# Jetson_Breakout.net
KiCad netlist of a schematic drawn in EAGLE
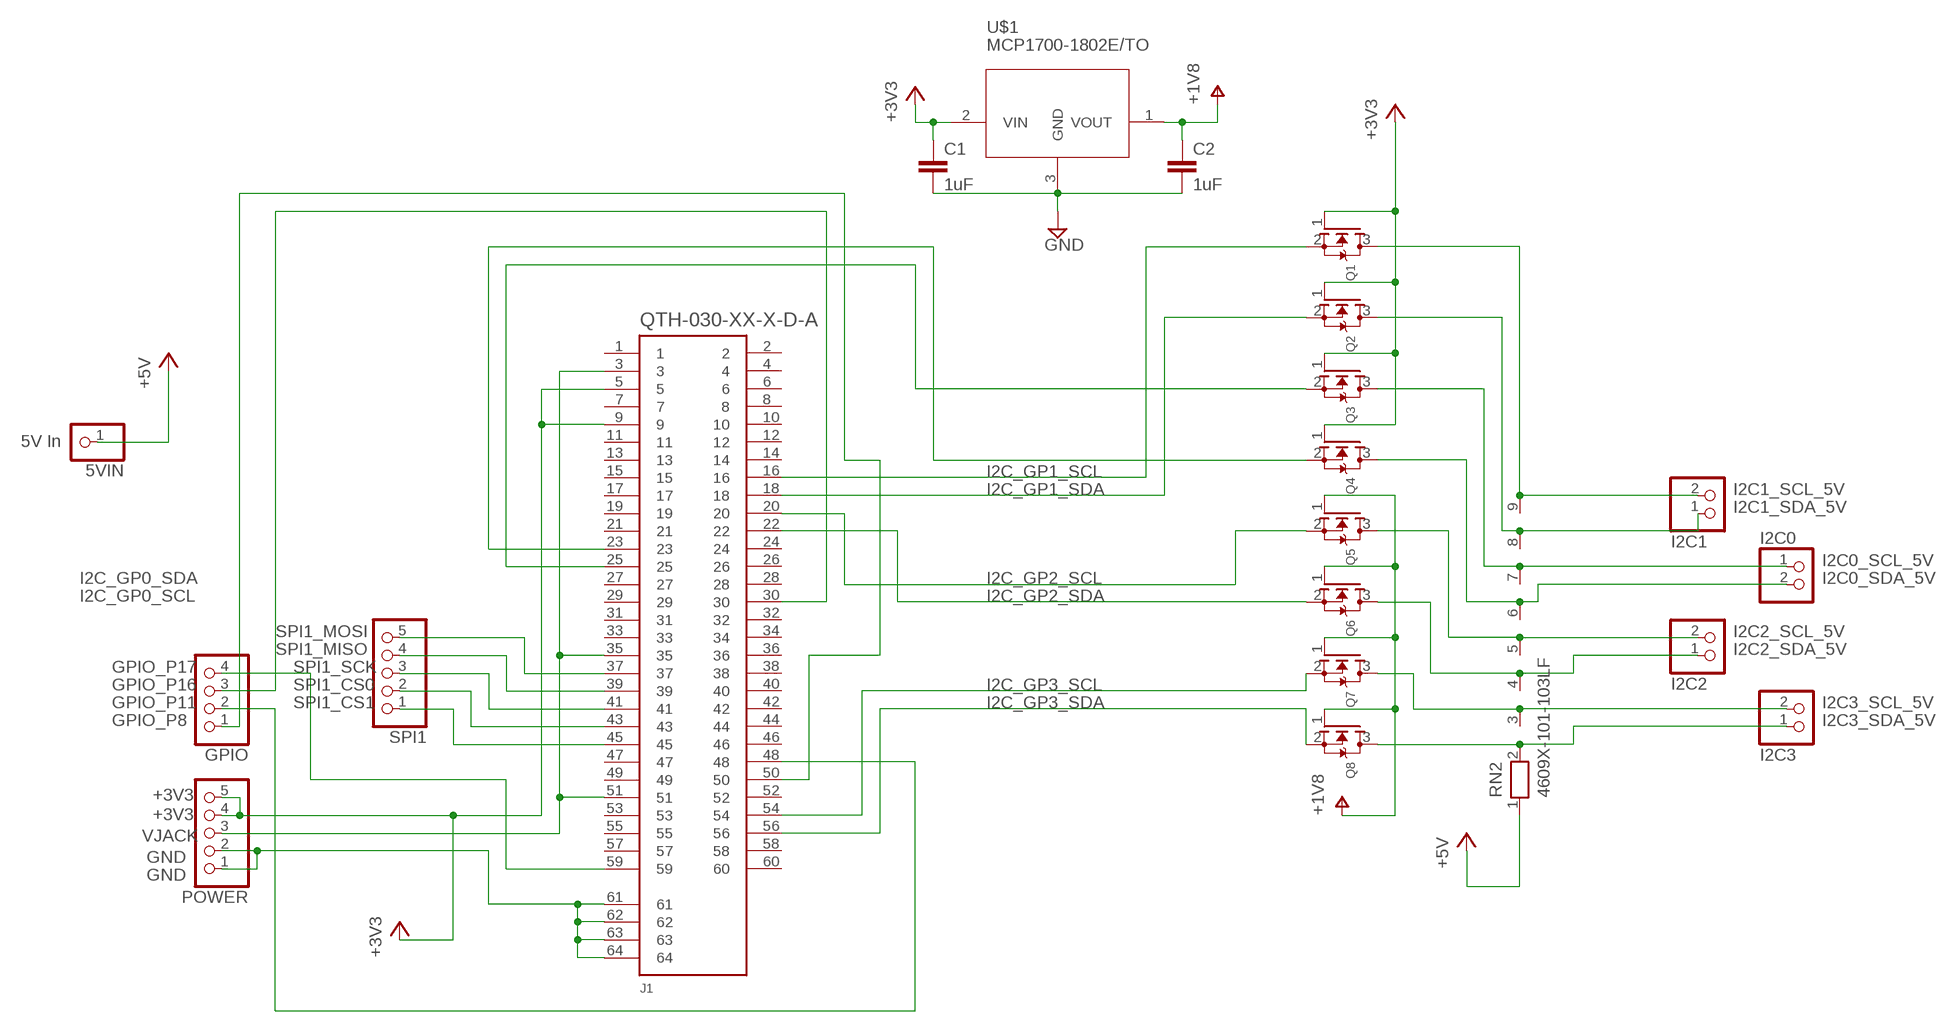
[diagram p0: schematic, sheet 1]

(export (version "E")
  (design (tool "Eeschema 10.0.6"))
  (components
    (comp (ref "5VIN")
      (value "PINHD-1X1")
      (footprint "eagle-import:1X01")
      (libsource (lib "eagle-import") (part "PINHD-1X1"))
    )
    (comp (ref "C1")
      (value "1uF")
      (footprint "eagle-import:C050-025X075")
      (libsource (lib "eagle-import") (part "C-EU050-025X075"))
    )
    (comp (ref "C2")
      (value "1uF")
      (footprint "eagle-import:C050-025X075")
      (libsource (lib "eagle-import") (part "C-EU050-025X075"))
    )
    (comp (ref "GPIO")
      (value "PINHD-1X4")
      (footprint "eagle-import:1X04")
      (libsource (lib "eagle-import") (part "PINHD-1X4"))
    )
    (comp (ref "I2C0")
      (value "PINHD-1X2")
      (footprint "eagle-import:1X02")
      (libsource (lib "eagle-import") (part "PINHD-1X2"))
    )
    (comp (ref "I2C1")
      (value "PINHD-1X2")
      (footprint "eagle-import:1X02")
      (libsource (lib "eagle-import") (part "PINHD-1X2"))
    )
    (comp (ref "I2C2")
      (value "PINHD-1X2")
      (footprint "eagle-import:1X02")
      (libsource (lib "eagle-import") (part "PINHD-1X2"))
    )
    (comp (ref "I2C3")
      (value "PINHD-1X2")
      (footprint "eagle-import:1X02")
      (libsource (lib "eagle-import") (part "PINHD-1X2"))
    )
    (comp (ref "J1")
      (value "QTH-030-XX-X-D-A")
      (footprint "eagle-import:QTH-030-XX-X-D-A")
      (libsource (lib "eagle-import") (part "QTH-030-XX-X-D-A"))
    )
    (comp (ref "POWER")
      (value "PINHD-1X5")
      (footprint "eagle-import:1X05")
      (libsource (lib "eagle-import") (part "PINHD-1X5"))
    )
    (comp (ref "Q1")
      (value "MOSFET-NREFLOW")
      (footprint "eagle-import:SOT23")
      (libsource (lib "eagle-import") (part "MOSFET-NREFLOW"))
    )
    (comp (ref "Q2")
      (value "MOSFET-NREFLOW")
      (footprint "eagle-import:SOT23")
      (libsource (lib "eagle-import") (part "MOSFET-NREFLOW"))
    )
    (comp (ref "Q3")
      (value "MOSFET-NREFLOW")
      (footprint "eagle-import:SOT23")
      (libsource (lib "eagle-import") (part "MOSFET-NREFLOW"))
    )
    (comp (ref "Q4")
      (value "MOSFET-NREFLOW")
      (footprint "eagle-import:SOT23")
      (libsource (lib "eagle-import") (part "MOSFET-NREFLOW"))
    )
    (comp (ref "Q5")
      (value "MOSFET-NREFLOW")
      (footprint "eagle-import:SOT23")
      (libsource (lib "eagle-import") (part "MOSFET-NREFLOW"))
    )
    (comp (ref "Q6")
      (value "MOSFET-NREFLOW")
      (footprint "eagle-import:SOT23")
      (libsource (lib "eagle-import") (part "MOSFET-NREFLOW"))
    )
    (comp (ref "Q7")
      (value "MOSFET-NREFLOW")
      (footprint "eagle-import:SOT23")
      (libsource (lib "eagle-import") (part "MOSFET-NREFLOW"))
    )
    (comp (ref "Q8")
      (value "MOSFET-NREFLOW")
      (footprint "eagle-import:SOT23")
      (libsource (lib "eagle-import") (part "MOSFET-NREFLOW"))
    )
    (comp (ref "RN2")
      (value "4609X-101-103LF")
      (footprint "eagle-import:RN-9")
      (libsource (lib "eagle-import") (part "RN08"))
    )
    (comp (ref "SPI1")
      (value "PINHD-1X5")
      (footprint "eagle-import:1X05")
      (libsource (lib "eagle-import") (part "PINHD-1X5"))
    )
    (comp (ref "U$1")
      (value "MCP1700-1802E/TO")
      (footprint "eagle-import:TO92")
      (libsource (lib "eagle-import") (part "MCP1700-1802E/TO"))
    )
  )
  (nets
    (net (code "1") (name "+1V8") (class "Default")
      (node (ref "C2") (pin "1") (pinfunction "1_1") (pintype "passive"))
      (node (ref "Q5") (pin "1") (pinfunction "G_1") (pintype "bidirectional"))
      (node (ref "Q6") (pin "1") (pinfunction "G_1") (pintype "bidirectional"))
      (node (ref "Q7") (pin "1") (pinfunction "G_1") (pintype "bidirectional"))
      (node (ref "Q8") (pin "1") (pinfunction "G_1") (pintype "bidirectional"))
      (node (ref "U$1") (pin "1") (pinfunction "VOUT_1") (pintype "power_in"))
    )
    (net (code "2") (name "+3V3") (class "Default")
      (node (ref "C1") (pin "1") (pinfunction "1_1") (pintype "passive"))
      (node (ref "J1") (pin "5") (pinfunction "5_5") (pintype "bidirectional"))
      (node (ref "J1") (pin "9") (pinfunction "9_9") (pintype "bidirectional"))
      (node (ref "POWER") (pin "4") (pinfunction "4_4") (pintype "passive"))
      (node (ref "POWER") (pin "5") (pinfunction "5_5") (pintype "passive"))
      (node (ref "Q1") (pin "1") (pinfunction "G_1") (pintype "bidirectional"))
      (node (ref "Q2") (pin "1") (pinfunction "G_1") (pintype "bidirectional"))
      (node (ref "Q3") (pin "1") (pinfunction "G_1") (pintype "bidirectional"))
      (node (ref "Q4") (pin "1") (pinfunction "G_1") (pintype "bidirectional"))
      (node (ref "U$1") (pin "2") (pinfunction "VIN_2") (pintype "power_in"))
    )
    (net (code "3") (name "+5V") (class "Default")
      (node (ref "5VIN") (pin "1") (pinfunction "1_1") (pintype "passive"))
      (node (ref "RN2") (pin "1") (pinfunction "1_1") (pintype "passive"))
    )
    (net (code "4") (name "/GPIO_P8") (class "Default")
      (node (ref "GPIO") (pin "1") (pinfunction "1_1") (pintype "passive"))
      (node (ref "J1") (pin "50") (pinfunction "50_50") (pintype "bidirectional"))
    )
    (net (code "5") (name "/GPIO_P11") (class "Default")
      (node (ref "GPIO") (pin "2") (pinfunction "2_2") (pintype "passive"))
      (node (ref "J1") (pin "48") (pinfunction "48_48") (pintype "bidirectional"))
    )
    (net (code "6") (name "/GPIO_P16") (class "Default")
      (node (ref "GPIO") (pin "3") (pinfunction "3_3") (pintype "passive"))
      (node (ref "J1") (pin "30") (pinfunction "30_30") (pintype "bidirectional"))
    )
    (net (code "7") (name "/GPIO_P17") (class "Default")
      (node (ref "GPIO") (pin "4") (pinfunction "4_4") (pintype "passive"))
      (node (ref "J1") (pin "59") (pinfunction "59_59") (pintype "bidirectional"))
    )
    (net (code "8") (name "/I2C0_SCL_5V") (class "Default")
      (node (ref "I2C0") (pin "1") (pinfunction "1_1") (pintype "passive"))
      (node (ref "Q3") (pin "3") (pinfunction "D_3") (pintype "bidirectional"))
      (node (ref "RN2") (pin "7") (pinfunction "7_7") (pintype "passive"))
    )
    (net (code "9") (name "/I2C0_SDA_5V") (class "Default")
      (node (ref "I2C0") (pin "2") (pinfunction "2_2") (pintype "passive"))
      (node (ref "Q4") (pin "3") (pinfunction "D_3") (pintype "bidirectional"))
      (node (ref "RN2") (pin "6") (pinfunction "6_6") (pintype "passive"))
    )
    (net (code "10") (name "/I2C1_SCL_5V") (class "Default")
      (node (ref "I2C1") (pin "2") (pinfunction "2_2") (pintype "passive"))
      (node (ref "Q1") (pin "3") (pinfunction "D_3") (pintype "bidirectional"))
      (node (ref "RN2") (pin "9") (pinfunction "9_9") (pintype "passive"))
    )
    (net (code "11") (name "/I2C1_SDA_5V") (class "Default")
      (node (ref "I2C1") (pin "1") (pinfunction "1_1") (pintype "passive"))
      (node (ref "Q2") (pin "3") (pinfunction "D_3") (pintype "bidirectional"))
      (node (ref "RN2") (pin "8") (pinfunction "8_8") (pintype "passive"))
    )
    (net (code "12") (name "/I2C2_SCL_5V") (class "Default")
      (node (ref "I2C2") (pin "2") (pinfunction "2_2") (pintype "passive"))
      (node (ref "Q5") (pin "3") (pinfunction "D_3") (pintype "bidirectional"))
      (node (ref "RN2") (pin "5") (pinfunction "5_5") (pintype "passive"))
    )
    (net (code "13") (name "/I2C2_SDA_5V") (class "Default")
      (node (ref "I2C2") (pin "1") (pinfunction "1_1") (pintype "passive"))
      (node (ref "Q6") (pin "3") (pinfunction "D_3") (pintype "bidirectional"))
      (node (ref "RN2") (pin "4") (pinfunction "4_4") (pintype "passive"))
    )
    (net (code "14") (name "/I2C3_SCL_5V") (class "Default")
      (node (ref "I2C3") (pin "2") (pinfunction "2_2") (pintype "passive"))
      (node (ref "Q7") (pin "3") (pinfunction "D_3") (pintype "bidirectional"))
      (node (ref "RN2") (pin "3") (pinfunction "3_3") (pintype "passive"))
    )
    (net (code "15") (name "/I2C3_SDA_5V") (class "Default")
      (node (ref "I2C3") (pin "1") (pinfunction "1_1") (pintype "passive"))
      (node (ref "Q8") (pin "3") (pinfunction "D_3") (pintype "bidirectional"))
      (node (ref "RN2") (pin "2") (pinfunction "2_2") (pintype "passive"))
    )
    (net (code "16") (name "/I2C_GP0_SCL") (class "Default")
      (node (ref "J1") (pin "25") (pinfunction "25_25") (pintype "bidirectional"))
      (node (ref "Q3") (pin "2") (pinfunction "S_2") (pintype "bidirectional"))
    )
    (net (code "17") (name "/I2C_GP0_SDA") (class "Default")
      (node (ref "J1") (pin "23") (pinfunction "23_23") (pintype "bidirectional"))
      (node (ref "Q4") (pin "2") (pinfunction "S_2") (pintype "bidirectional"))
    )
    (net (code "18") (name "/I2C_GP1_SCL") (class "Default")
      (node (ref "J1") (pin "16") (pinfunction "16_16") (pintype "bidirectional"))
      (node (ref "Q1") (pin "2") (pinfunction "S_2") (pintype "bidirectional"))
    )
    (net (code "19") (name "/I2C_GP1_SDA") (class "Default")
      (node (ref "J1") (pin "18") (pinfunction "18_18") (pintype "bidirectional"))
      (node (ref "Q2") (pin "2") (pinfunction "S_2") (pintype "bidirectional"))
    )
    (net (code "20") (name "/I2C_GP2_SCL") (class "Default")
      (node (ref "J1") (pin "20") (pinfunction "20_20") (pintype "bidirectional"))
      (node (ref "Q5") (pin "2") (pinfunction "S_2") (pintype "bidirectional"))
    )
    (net (code "21") (name "/I2C_GP2_SDA") (class "Default")
      (node (ref "J1") (pin "22") (pinfunction "22_22") (pintype "bidirectional"))
      (node (ref "Q6") (pin "2") (pinfunction "S_2") (pintype "bidirectional"))
    )
    (net (code "22") (name "/I2C_GP3_SCL") (class "Default")
      (node (ref "J1") (pin "54") (pinfunction "54_54") (pintype "bidirectional"))
      (node (ref "Q7") (pin "2") (pinfunction "S_2") (pintype "bidirectional"))
    )
    (net (code "23") (name "/I2C_GP3_SDA") (class "Default")
      (node (ref "J1") (pin "56") (pinfunction "56_56") (pintype "bidirectional"))
      (node (ref "Q8") (pin "2") (pinfunction "S_2") (pintype "bidirectional"))
    )
    (net (code "24") (name "/SPI1_CS0") (class "Default")
      (node (ref "J1") (pin "43") (pinfunction "43_43") (pintype "bidirectional"))
      (node (ref "SPI1") (pin "2") (pinfunction "2_2") (pintype "passive"))
    )
    (net (code "25") (name "/SPI1_CS1") (class "Default")
      (node (ref "J1") (pin "45") (pinfunction "45_45") (pintype "bidirectional"))
      (node (ref "SPI1") (pin "1") (pinfunction "1_1") (pintype "passive"))
    )
    (net (code "26") (name "/SPI1_MISO") (class "Default")
      (node (ref "J1") (pin "39") (pinfunction "39_39") (pintype "bidirectional"))
      (node (ref "SPI1") (pin "4") (pinfunction "4_4") (pintype "passive"))
    )
    (net (code "27") (name "/SPI1_MOSI") (class "Default")
      (node (ref "J1") (pin "37") (pinfunction "37_37") (pintype "bidirectional"))
      (node (ref "SPI1") (pin "5") (pinfunction "5_5") (pintype "passive"))
    )
    (net (code "28") (name "/SPI1_SCK") (class "Default")
      (node (ref "J1") (pin "41") (pinfunction "41_41") (pintype "bidirectional"))
      (node (ref "SPI1") (pin "3") (pinfunction "3_3") (pintype "passive"))
    )
    (net (code "29") (name "/VJACK") (class "Default")
      (node (ref "J1") (pin "3") (pinfunction "3_3") (pintype "bidirectional"))
      (node (ref "J1") (pin "35") (pinfunction "35_35") (pintype "bidirectional"))
      (node (ref "J1") (pin "51") (pinfunction "51_51") (pintype "bidirectional"))
      (node (ref "POWER") (pin "3") (pinfunction "3_3") (pintype "passive"))
    )
    (net (code "30") (name "GND") (class "Default")
      (node (ref "C1") (pin "2") (pinfunction "2_2") (pintype "passive"))
      (node (ref "C2") (pin "2") (pinfunction "2_2") (pintype "passive"))
      (node (ref "J1") (pin "61") (pinfunction "61_61") (pintype "power_in"))
      (node (ref "J1") (pin "62") (pinfunction "62_62") (pintype "power_in"))
      (node (ref "J1") (pin "63") (pinfunction "63_63") (pintype "power_in"))
      (node (ref "J1") (pin "64") (pinfunction "64_64") (pintype "power_in"))
      (node (ref "POWER") (pin "1") (pinfunction "1_1") (pintype "passive"))
      (node (ref "POWER") (pin "2") (pinfunction "2_2") (pintype "passive"))
      (node (ref "U$1") (pin "3") (pinfunction "GND_3") (pintype "power_in"))
    )
    (net (code "31") (name "unconnected-(J1-Pad1)") (class "Default")
      (node (ref "J1") (pin "1") (pinfunction "1_1") (pintype "bidirectional"))
    )
    (net (code "32") (name "unconnected-(J1-Pad2)") (class "Default")
      (node (ref "J1") (pin "2") (pinfunction "2_2") (pintype "bidirectional"))
    )
    (net (code "33") (name "unconnected-(J1-Pad4)") (class "Default")
      (node (ref "J1") (pin "4") (pinfunction "4_4") (pintype "bidirectional"))
    )
    (net (code "34") (name "unconnected-(J1-Pad6)") (class "Default")
      (node (ref "J1") (pin "6") (pinfunction "6_6") (pintype "bidirectional"))
    )
    (net (code "35") (name "unconnected-(J1-Pad7)") (class "Default")
      (node (ref "J1") (pin "7") (pinfunction "7_7") (pintype "bidirectional"))
    )
    (net (code "36") (name "unconnected-(J1-Pad8)") (class "Default")
      (node (ref "J1") (pin "8") (pinfunction "8_8") (pintype "bidirectional"))
    )
    (net (code "37") (name "unconnected-(J1-Pad10)") (class "Default")
      (node (ref "J1") (pin "10") (pinfunction "10_10") (pintype "bidirectional"))
    )
    (net (code "38") (name "unconnected-(J1-Pad11)") (class "Default")
      (node (ref "J1") (pin "11") (pinfunction "11_11") (pintype "bidirectional"))
    )
    (net (code "39") (name "unconnected-(J1-Pad12)") (class "Default")
      (node (ref "J1") (pin "12") (pinfunction "12_12") (pintype "bidirectional"))
    )
    (net (code "40") (name "unconnected-(J1-Pad13)") (class "Default")
      (node (ref "J1") (pin "13") (pinfunction "13_13") (pintype "bidirectional"))
    )
    (net (code "41") (name "unconnected-(J1-Pad14)") (class "Default")
      (node (ref "J1") (pin "14") (pinfunction "14_14") (pintype "bidirectional"))
    )
    (net (code "42") (name "unconnected-(J1-Pad15)") (class "Default")
      (node (ref "J1") (pin "15") (pinfunction "15_15") (pintype "bidirectional"))
    )
    (net (code "43") (name "unconnected-(J1-Pad17)") (class "Default")
      (node (ref "J1") (pin "17") (pinfunction "17_17") (pintype "bidirectional"))
    )
    (net (code "44") (name "unconnected-(J1-Pad19)") (class "Default")
      (node (ref "J1") (pin "19") (pinfunction "19_19") (pintype "bidirectional"))
    )
    (net (code "45") (name "unconnected-(J1-Pad21)") (class "Default")
      (node (ref "J1") (pin "21") (pinfunction "21_21") (pintype "bidirectional"))
    )
    (net (code "46") (name "unconnected-(J1-Pad24)") (class "Default")
      (node (ref "J1") (pin "24") (pinfunction "24_24") (pintype "bidirectional"))
    )
    (net (code "47") (name "unconnected-(J1-Pad26)") (class "Default")
      (node (ref "J1") (pin "26") (pinfunction "26_26") (pintype "bidirectional"))
    )
    (net (code "48") (name "unconnected-(J1-Pad27)") (class "Default")
      (node (ref "J1") (pin "27") (pinfunction "27_27") (pintype "bidirectional"))
    )
    (net (code "49") (name "unconnected-(J1-Pad28)") (class "Default")
      (node (ref "J1") (pin "28") (pinfunction "28_28") (pintype "bidirectional"))
    )
    (net (code "50") (name "unconnected-(J1-Pad29)") (class "Default")
      (node (ref "J1") (pin "29") (pinfunction "29_29") (pintype "bidirectional"))
    )
    (net (code "51") (name "unconnected-(J1-Pad31)") (class "Default")
      (node (ref "J1") (pin "31") (pinfunction "31_31") (pintype "bidirectional"))
    )
    (net (code "52") (name "unconnected-(J1-Pad32)") (class "Default")
      (node (ref "J1") (pin "32") (pinfunction "32_32") (pintype "bidirectional"))
    )
    (net (code "53") (name "unconnected-(J1-Pad33)") (class "Default")
      (node (ref "J1") (pin "33") (pinfunction "33_33") (pintype "bidirectional"))
    )
    (net (code "54") (name "unconnected-(J1-Pad34)") (class "Default")
      (node (ref "J1") (pin "34") (pinfunction "34_34") (pintype "bidirectional"))
    )
    (net (code "55") (name "unconnected-(J1-Pad36)") (class "Default")
      (node (ref "J1") (pin "36") (pinfunction "36_36") (pintype "bidirectional"))
    )
    (net (code "56") (name "unconnected-(J1-Pad38)") (class "Default")
      (node (ref "J1") (pin "38") (pinfunction "38_38") (pintype "bidirectional"))
    )
    (net (code "57") (name "unconnected-(J1-Pad40)") (class "Default")
      (node (ref "J1") (pin "40") (pinfunction "40_40") (pintype "bidirectional"))
    )
    (net (code "58") (name "unconnected-(J1-Pad42)") (class "Default")
      (node (ref "J1") (pin "42") (pinfunction "42_42") (pintype "bidirectional"))
    )
    (net (code "59") (name "unconnected-(J1-Pad44)") (class "Default")
      (node (ref "J1") (pin "44") (pinfunction "44_44") (pintype "bidirectional"))
    )
    (net (code "60") (name "unconnected-(J1-Pad46)") (class "Default")
      (node (ref "J1") (pin "46") (pinfunction "46_46") (pintype "bidirectional"))
    )
    (net (code "61") (name "unconnected-(J1-Pad47)") (class "Default")
      (node (ref "J1") (pin "47") (pinfunction "47_47") (pintype "bidirectional"))
    )
    (net (code "62") (name "unconnected-(J1-Pad49)") (class "Default")
      (node (ref "J1") (pin "49") (pinfunction "49_49") (pintype "bidirectional"))
    )
    (net (code "63") (name "unconnected-(J1-Pad52)") (class "Default")
      (node (ref "J1") (pin "52") (pinfunction "52_52") (pintype "bidirectional"))
    )
    (net (code "64") (name "unconnected-(J1-Pad53)") (class "Default")
      (node (ref "J1") (pin "53") (pinfunction "53_53") (pintype "bidirectional"))
    )
    (net (code "65") (name "unconnected-(J1-Pad55)") (class "Default")
      (node (ref "J1") (pin "55") (pinfunction "55_55") (pintype "bidirectional"))
    )
    (net (code "66") (name "unconnected-(J1-Pad57)") (class "Default")
      (node (ref "J1") (pin "57") (pinfunction "57_57") (pintype "bidirectional"))
    )
    (net (code "67") (name "unconnected-(J1-Pad58)") (class "Default")
      (node (ref "J1") (pin "58") (pinfunction "58_58") (pintype "bidirectional"))
    )
    (net (code "68") (name "unconnected-(J1-Pad60)") (class "Default")
      (node (ref "J1") (pin "60") (pinfunction "60_60") (pintype "bidirectional"))
    )
  )
)
